# Relay_PCB_v1.net
KiCad netlist of a schematic drawn in EAGLE
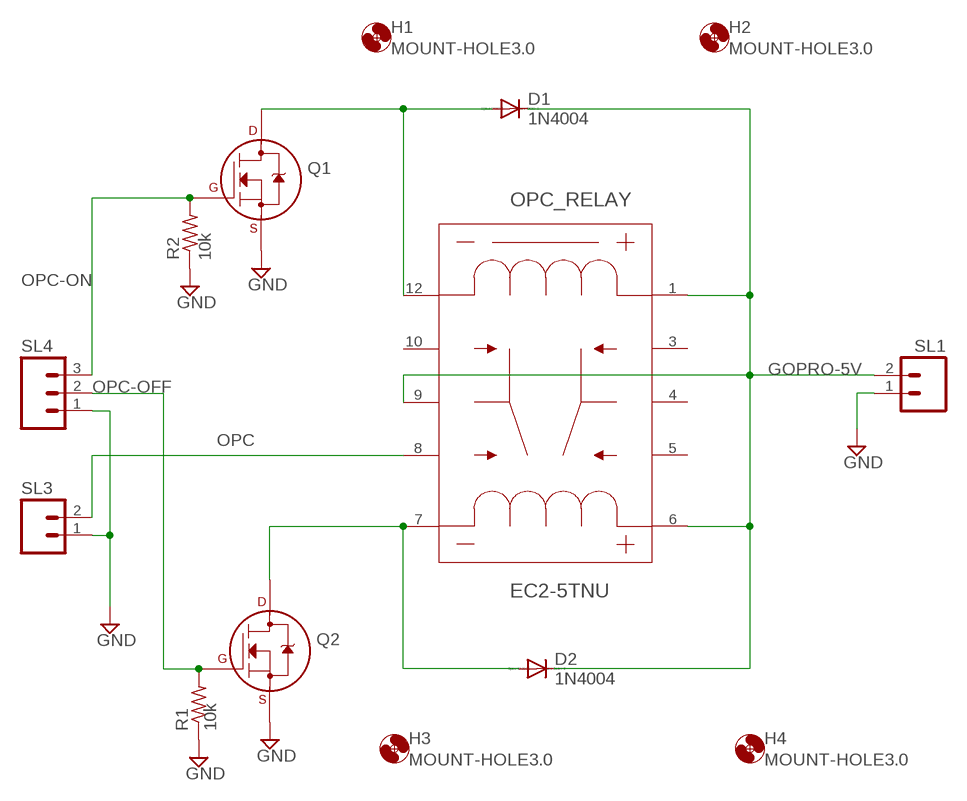
[diagram p0: schematic, sheet 1]

(export (version "E")
  (design (tool "Eeschema 10.0.6"))
  (components
    (comp (ref "D1")
      (value "1N4004")
      (footprint "eagle-import:DO41-10")
      (libsource (lib "eagle-import") (part "1N4004"))
    )
    (comp (ref "D2")
      (value "1N4004")
      (footprint "eagle-import:DO41-10")
      (libsource (lib "eagle-import") (part "1N4004"))
    )
    (comp (ref "H1")
      (value "MOUNT-HOLE3.0")
      (footprint "eagle-import:3,0")
      (libsource (lib "eagle-import") (part "MOUNT-HOLE3.0"))
    )
    (comp (ref "H2")
      (value "MOUNT-HOLE3.0")
      (footprint "eagle-import:3,0")
      (libsource (lib "eagle-import") (part "MOUNT-HOLE3.0"))
    )
    (comp (ref "H3")
      (value "MOUNT-HOLE3.0")
      (footprint "eagle-import:3,0")
      (libsource (lib "eagle-import") (part "MOUNT-HOLE3.0"))
    )
    (comp (ref "H4")
      (value "MOUNT-HOLE3.0")
      (footprint "eagle-import:3,0")
      (libsource (lib "eagle-import") (part "MOUNT-HOLE3.0"))
    )
    (comp (ref "OPC_RELAY")
      (value "EC2-5TNU")
      (footprint "eagle-import:EC2TNU")
      (fields (field (name "MANUFACTURER_PART_NUMBER") "EC25TNU"))
      (libsource (lib "eagle-import") (part "EC2-5TNU"))
    )
    (comp (ref "Q1")
      (value "2N7000_TO92")
      (footprint "eagle-import:TO-92")
      (libsource (lib "eagle-import") (part "2N700_TO920"))
    )
    (comp (ref "Q2")
      (value "2N7000_TO92")
      (footprint "eagle-import:TO-92")
      (libsource (lib "eagle-import") (part "2N700_TO920"))
    )
    (comp (ref "R1")
      (value "R-US_0207/7")
      (footprint "eagle-import:0207_7")
      (libsource (lib "eagle-import") (part "R-US_0207/7"))
    )
    (comp (ref "R2")
      (value "R-US_0207/7")
      (footprint "eagle-import:0207_7")
      (libsource (lib "eagle-import") (part "R-US_0207/7"))
    )
    (comp (ref "SL1")
      (value "M02")
      (footprint "eagle-import:02P")
      (libsource (lib "eagle-import") (part "M02"))
    )
    (comp (ref "SL3")
      (value "M02")
      (footprint "eagle-import:02P")
      (libsource (lib "eagle-import") (part "M02"))
    )
    (comp (ref "SL4")
      (value "M03")
      (footprint "eagle-import:03P")
      (libsource (lib "eagle-import") (part "M03"))
    )
  )
  (nets
    (net (code "1") (name "/GOPRO-5V") (class "Default")
      (node (ref "D1") (pin "C") (pinfunction "C_C") (pintype "passive"))
      (node (ref "D2") (pin "C") (pinfunction "C_C") (pintype "passive"))
      (node (ref "OPC_RELAY") (pin "1") (pinfunction "1_1") (pintype "passive"))
      (node (ref "OPC_RELAY") (pin "6") (pinfunction "5_6") (pintype "passive"))
      (node (ref "OPC_RELAY") (pin "9") (pinfunction "8_9") (pintype "passive"))
      (node (ref "SL1") (pin "2") (pinfunction "2_2") (pintype "passive"))
    )
    (net (code "2") (name "/OPC") (class "Default")
      (node (ref "OPC_RELAY") (pin "8") (pinfunction "7_8") (pintype "passive"))
      (node (ref "SL3") (pin "2") (pinfunction "2_2") (pintype "passive"))
    )
    (net (code "3") (name "/OPC-OFF") (class "Default")
      (node (ref "Q2") (pin "2") (pinfunction "G_2") (pintype "tri_state"))
      (node (ref "R1") (pin "2") (pinfunction "2_2") (pintype "passive"))
      (node (ref "SL4") (pin "2") (pinfunction "2_2") (pintype "passive"))
    )
    (net (code "4") (name "/OPC-ON") (class "Default")
      (node (ref "Q1") (pin "2") (pinfunction "G_2") (pintype "tri_state"))
      (node (ref "R2") (pin "2") (pinfunction "2_2") (pintype "passive"))
      (node (ref "SL4") (pin "3") (pinfunction "3_3") (pintype "passive"))
    )
    (net (code "5") (name "GND") (class "Default")
      (node (ref "Q1") (pin "1") (pinfunction "S_1") (pintype "bidirectional"))
      (node (ref "Q2") (pin "1") (pinfunction "S_1") (pintype "bidirectional"))
      (node (ref "R1") (pin "1") (pinfunction "1_1") (pintype "passive"))
      (node (ref "R2") (pin "1") (pinfunction "1_1") (pintype "passive"))
      (node (ref "SL1") (pin "1") (pinfunction "1_1") (pintype "passive"))
      (node (ref "SL3") (pin "1") (pinfunction "1_1") (pintype "passive"))
      (node (ref "SL4") (pin "1") (pinfunction "1_1") (pintype "passive"))
    )
    (net (code "6") (name "Net-(OPC_RELAY-6)") (class "Default")
      (node (ref "D2") (pin "A") (pinfunction "A_A") (pintype "passive"))
      (node (ref "OPC_RELAY") (pin "7") (pinfunction "6_7") (pintype "passive"))
      (node (ref "Q2") (pin "3") (pinfunction "D_3") (pintype "bidirectional"))
    )
    (net (code "7") (name "Net-(OPC_RELAY-10)") (class "Default")
      (node (ref "D1") (pin "A") (pinfunction "A_A") (pintype "passive"))
      (node (ref "OPC_RELAY") (pin "12") (pinfunction "10_12") (pintype "passive"))
      (node (ref "Q1") (pin "3") (pinfunction "D_3") (pintype "bidirectional"))
    )
    (net (code "8") (name "unconnected-(OPC_RELAY-2-Pad3)") (class "Default")
      (node (ref "OPC_RELAY") (pin "3") (pinfunction "2_3") (pintype "passive"))
    )
    (net (code "9") (name "unconnected-(OPC_RELAY-3-Pad4)") (class "Default")
      (node (ref "OPC_RELAY") (pin "4") (pinfunction "3_4") (pintype "passive"))
    )
    (net (code "10") (name "unconnected-(OPC_RELAY-4-Pad5)") (class "Default")
      (node (ref "OPC_RELAY") (pin "5") (pinfunction "4_5") (pintype "passive"))
    )
    (net (code "11") (name "unconnected-(OPC_RELAY-9-Pad10)") (class "Default")
      (node (ref "OPC_RELAY") (pin "10") (pinfunction "9_10") (pintype "passive"))
    )
  )
)
